# PROTO0001.net
KiCad netlist of a schematic drawn in EAGLE
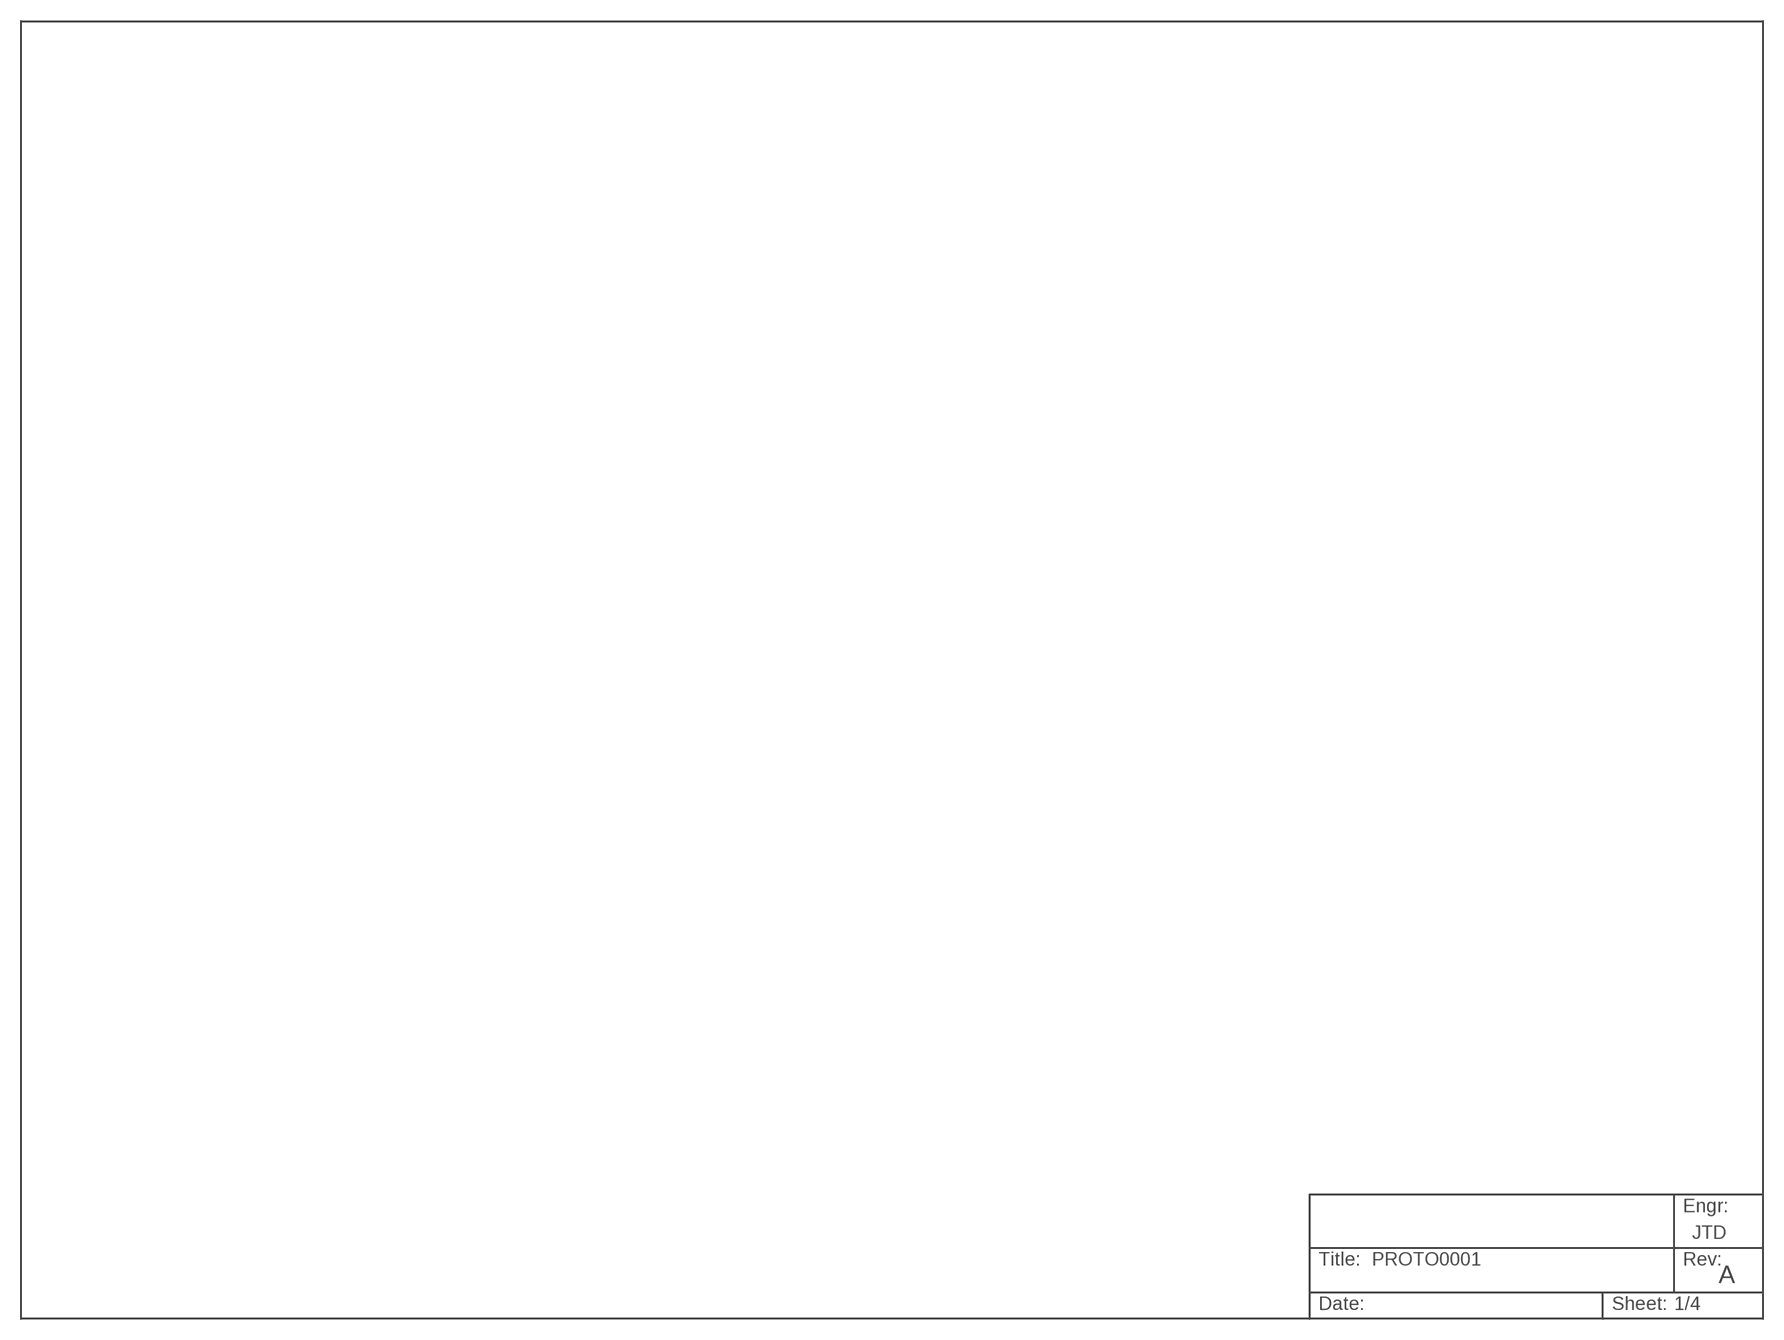
[diagram p0: schematic, sheet 1]
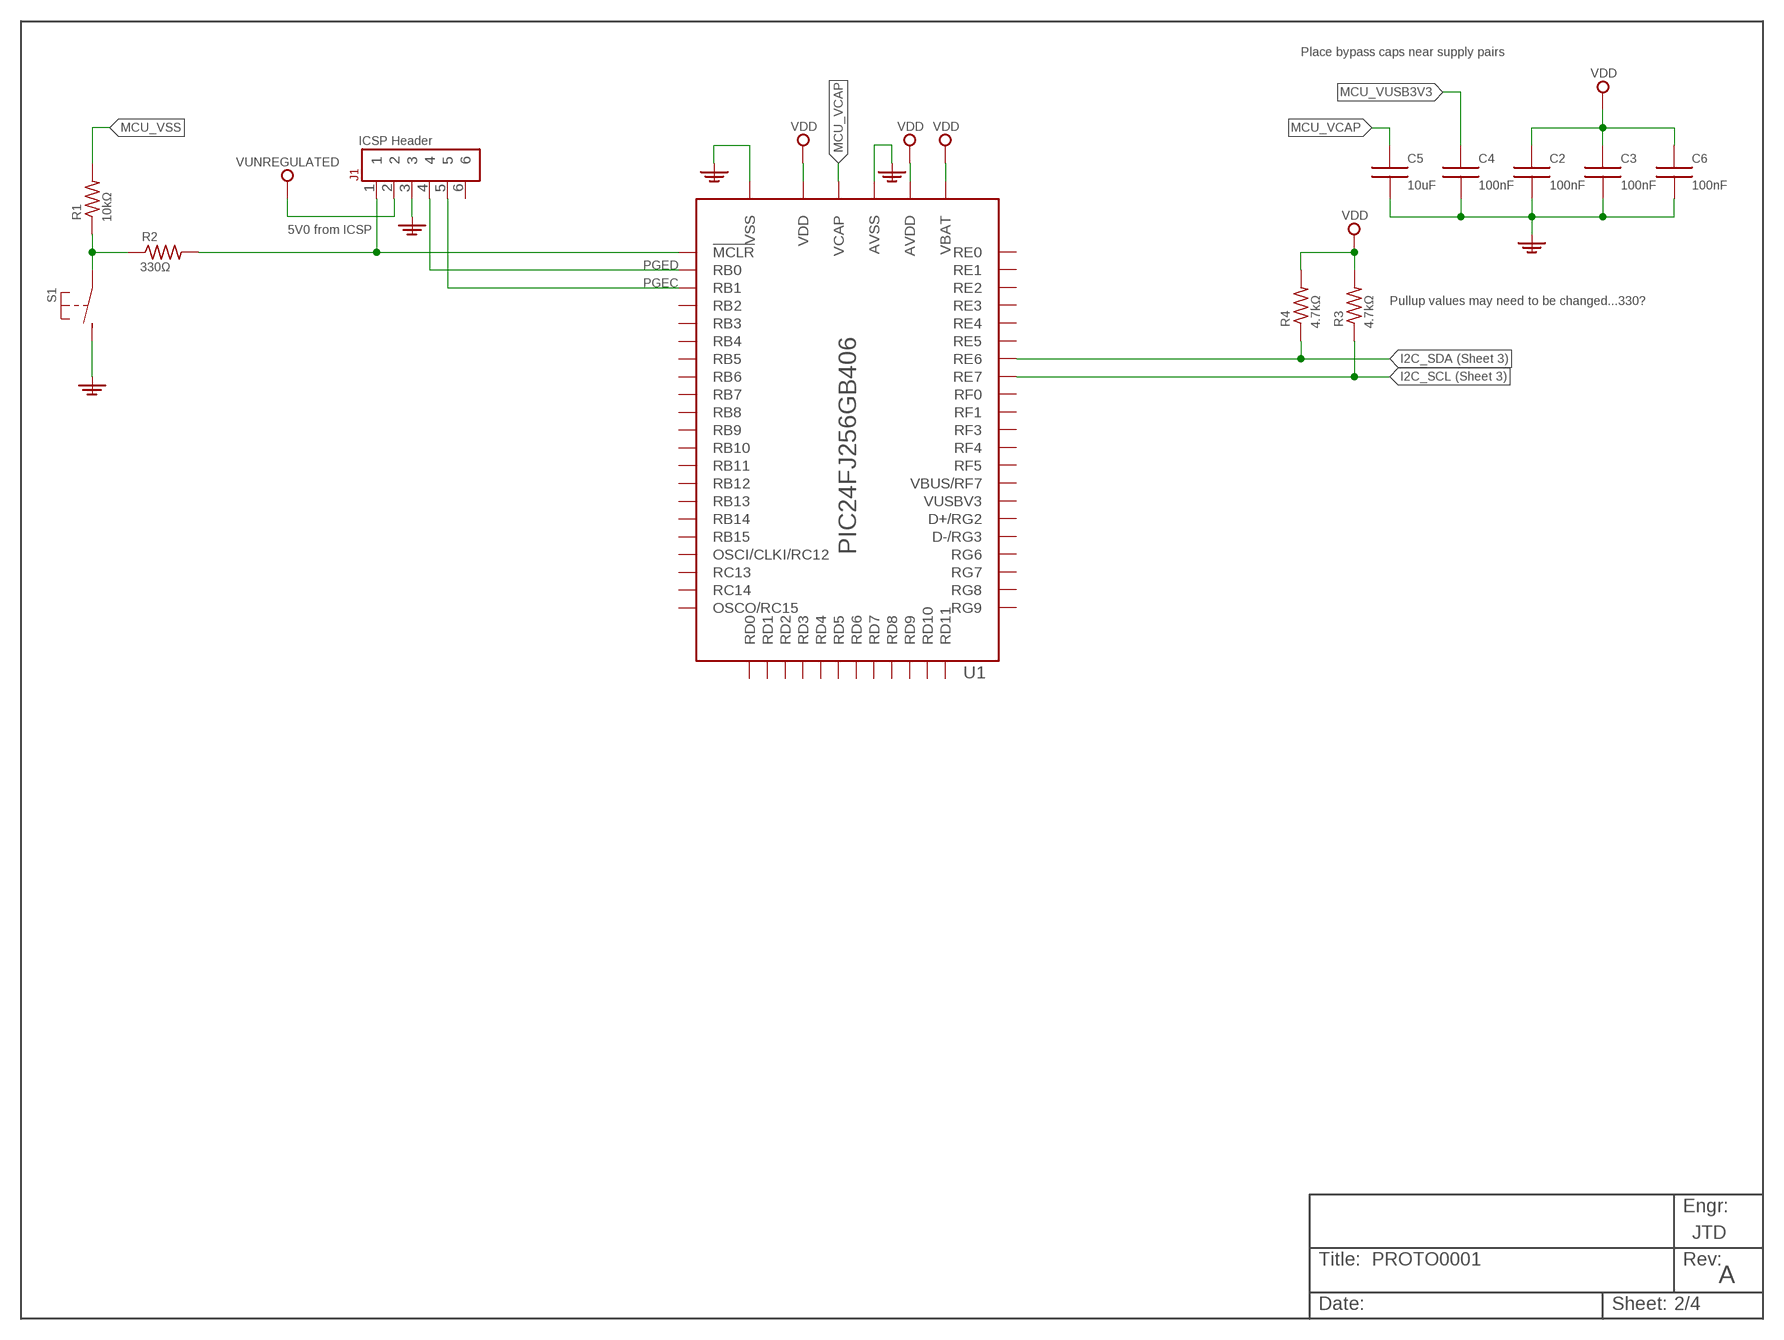
[diagram p1: schematic, sheet 2]
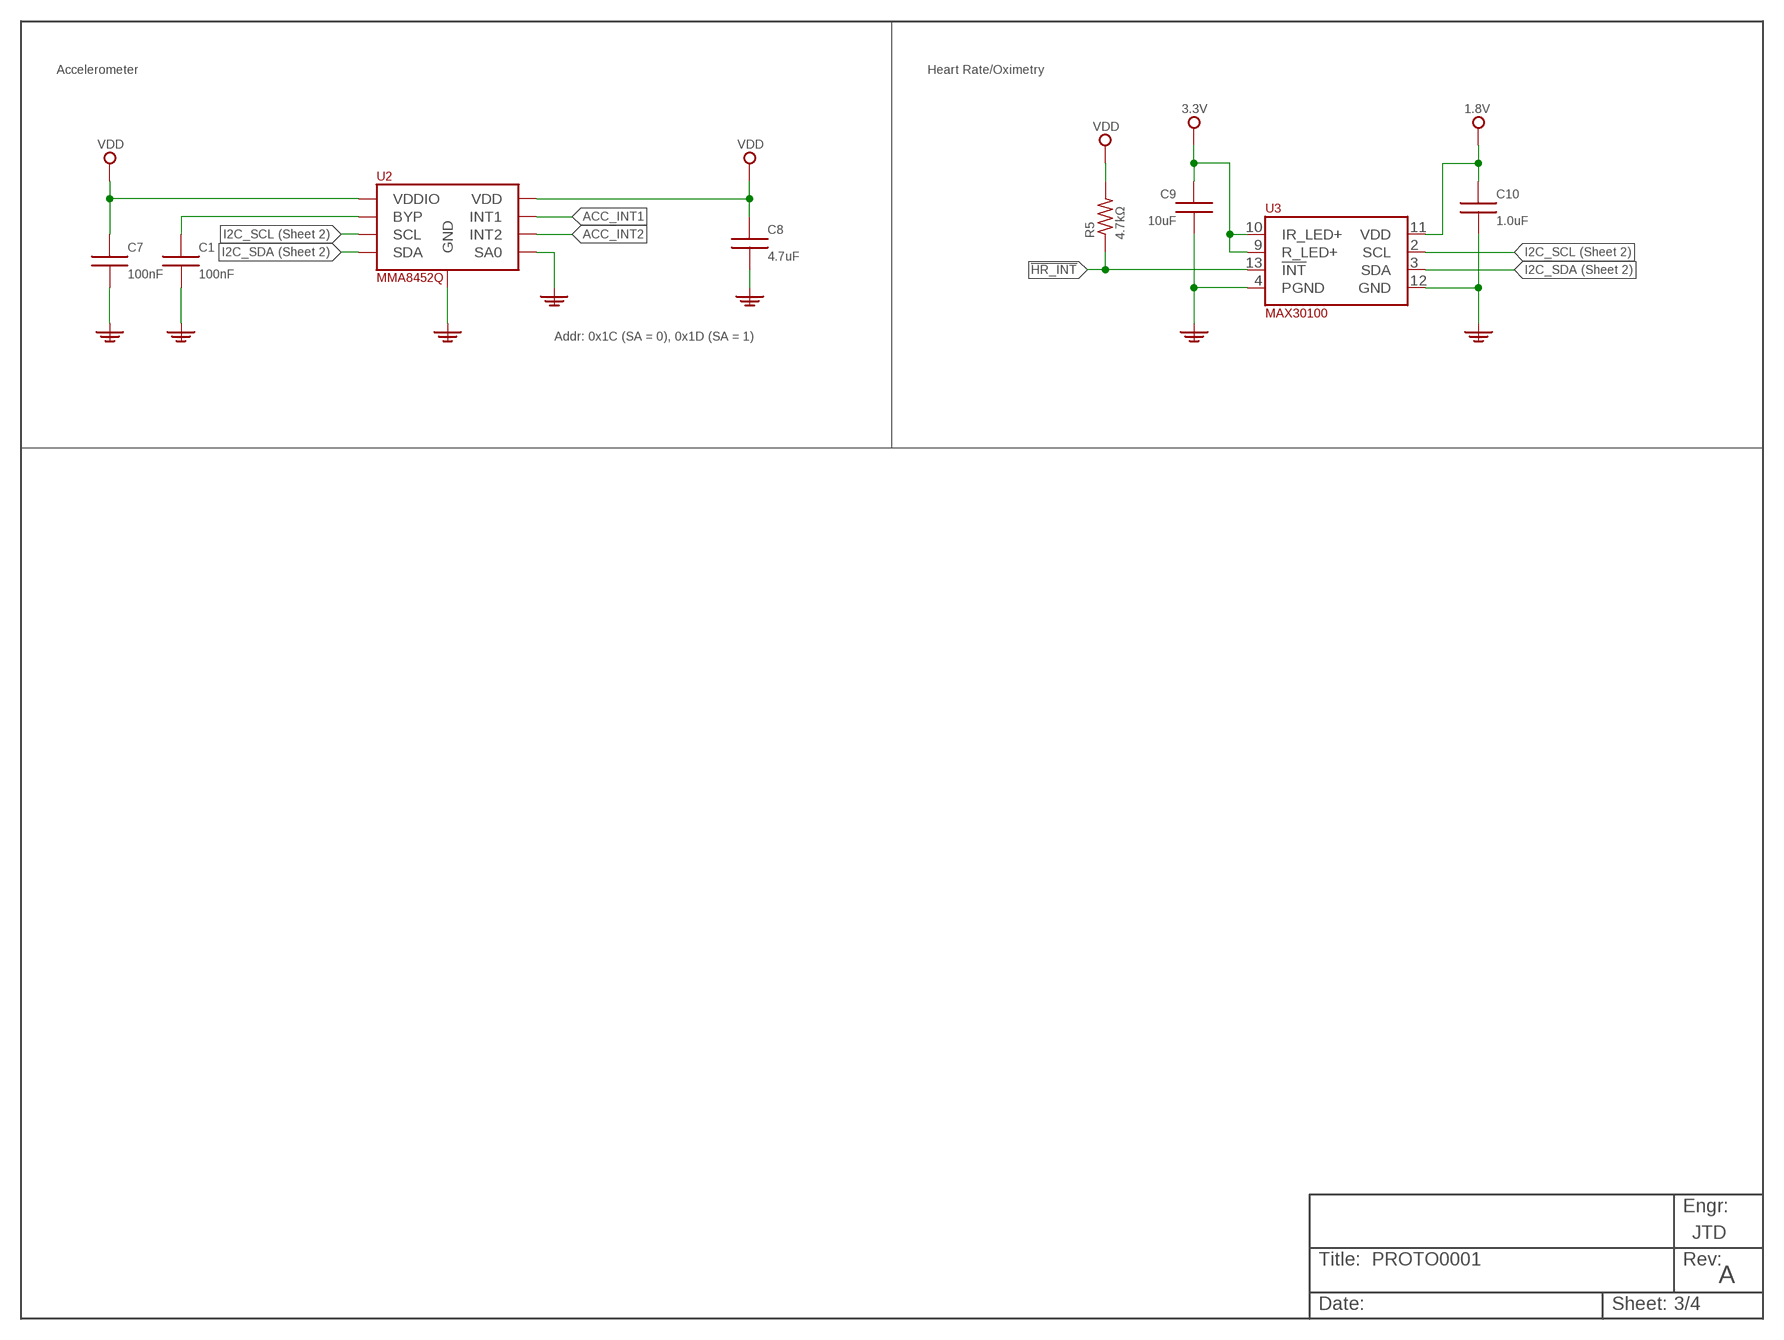
[diagram p2: schematic, sheet 3]
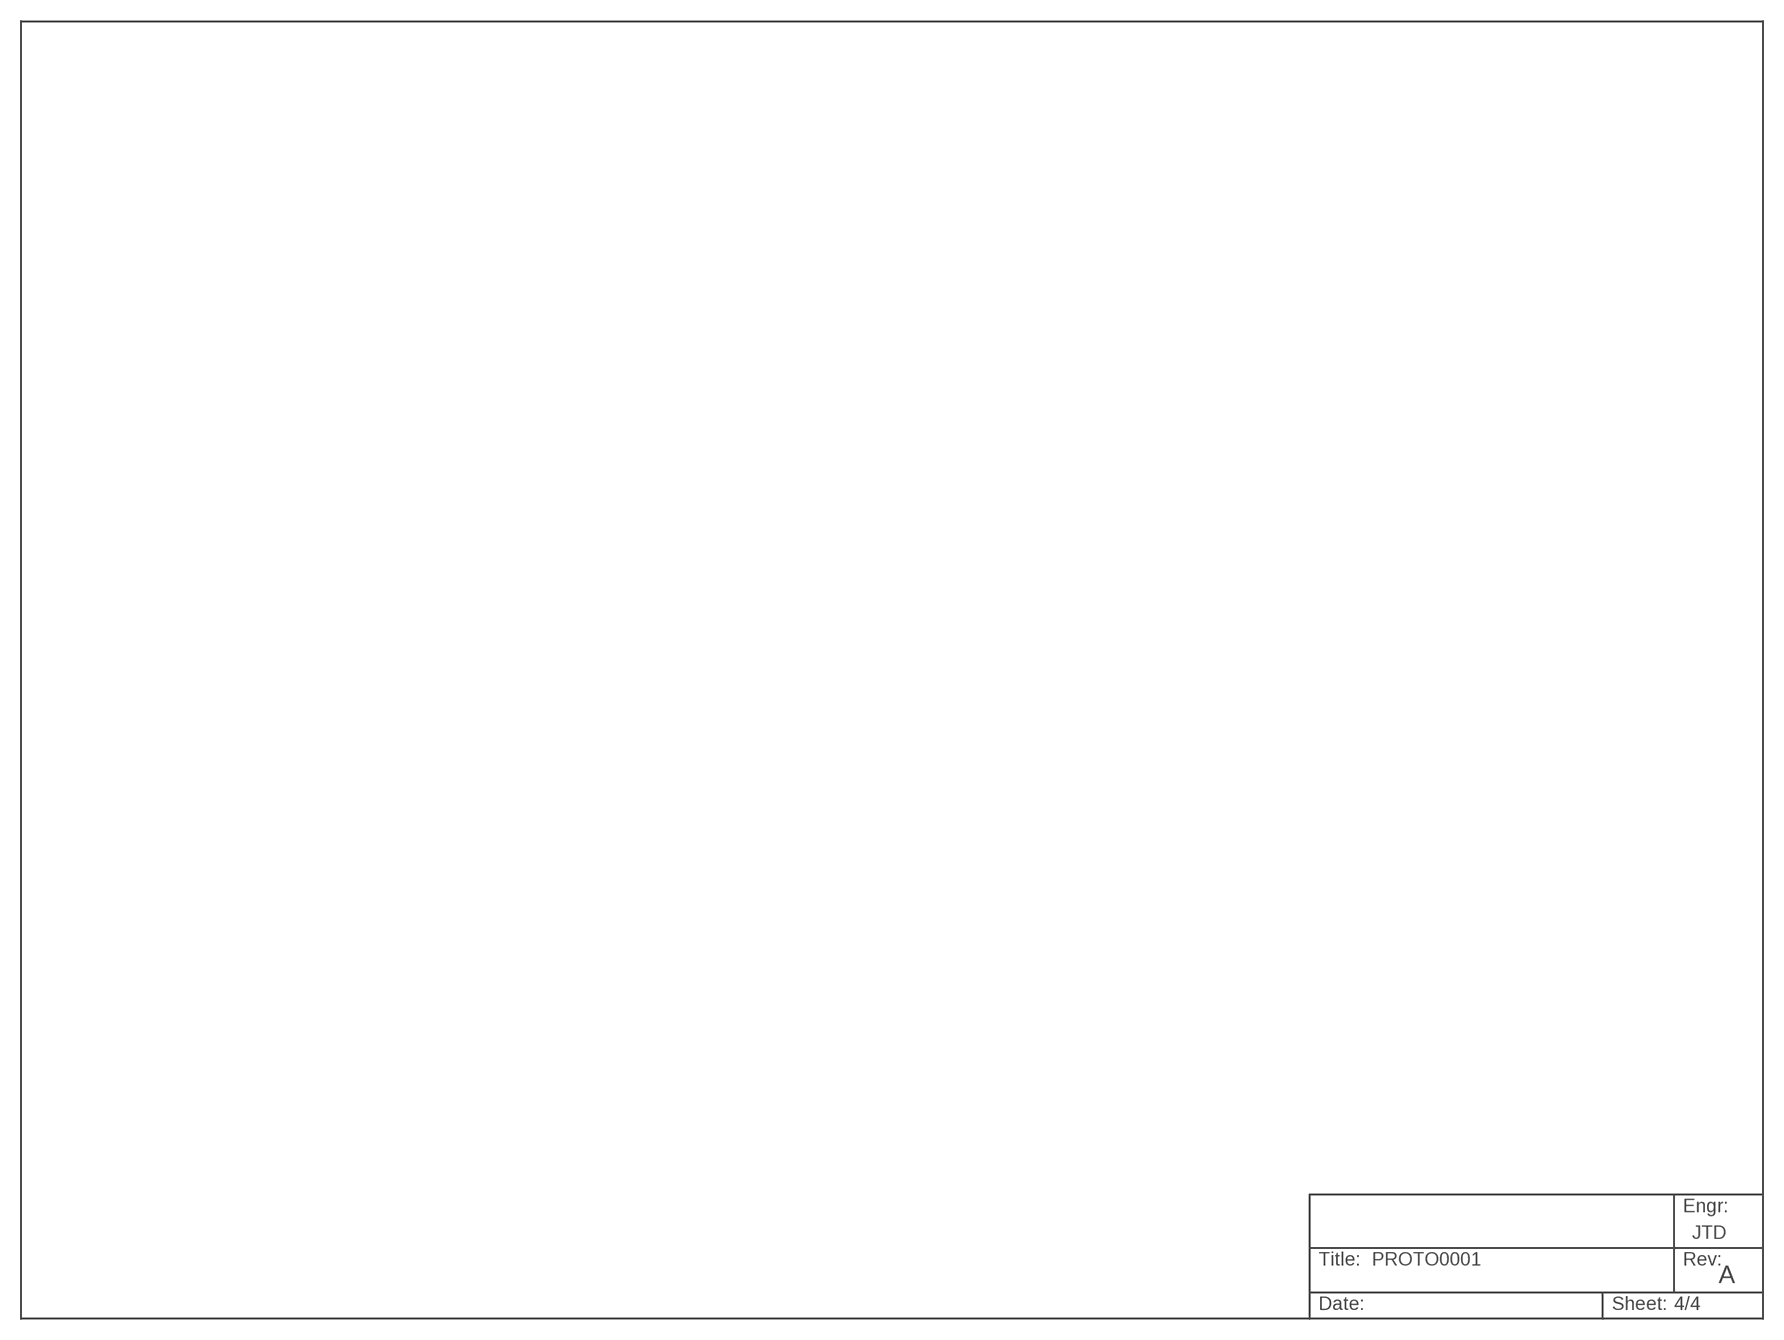
[diagram p3: schematic, sheet 4]

(export (version "E")
  (design (tool "Eeschema 10.0.6"))
  (components
    (comp (ref "C1")
      (value "CAP_100N_0402_CERAMIC")
      (footprint "eagle-import:CAPACITOR_0402")
      (fields
        (field (name "MANUFACTURER") "AVX Corporation")
        (field (name "PARTNO") "04023C104KAT2A")
        (field (name "TOLERANCE") "10%")
      )
      (libsource (lib "eagle-import") (part "CAP_100N_0402_CERAMIC"))
    )
    (comp (ref "C7")
      (value "CAP_100N_0402_CERAMIC")
      (footprint "eagle-import:CAPACITOR_0402")
      (fields
        (field (name "MANUFACTURER") "AVX Corporation")
        (field (name "PARTNO") "04023C104KAT2A")
        (field (name "TOLERANCE") "10%")
      )
      (libsource (lib "eagle-import") (part "CAP_100N_0402_CERAMIC"))
    )
    (comp (ref "C8")
      (value "CAP_4.7U_0603_CERAMIC")
      (footprint "eagle-import:CAPACITOR_0603")
      (fields
        (field (name "MANUFACTURER") "Murata Electronics")
        (field (name "PARTNO") "GRM188R61A475KE15D")
        (field (name "TOLERANCE") "10%")
      )
      (libsource (lib "eagle-import") (part "CAP_4.7U_0603_CERAMIC"))
    )
    (comp (ref "C9")
      (value "CAP_10U_0805_CERAMIC")
      (footprint "eagle-import:CAPACITOR_0805")
      (fields (field (name "MANUFACTURER") "AVX Corporation") (field (name "PARTNO") "0805YD106KAT2A"))
      (libsource (lib "eagle-import") (part "CAP_10U_0805_CERAMIC"))
    )
    (comp (ref "C10")
      (value "CAP_1U_0603_CERAMIC")
      (footprint "eagle-import:CAPACITOR_0603")
      (fields (field (name "MANUFACTURER") "Murata Electronics") (field (name "TOLERANCE") "10%"))
      (libsource (lib "eagle-import") (part "CAP_1U_0603_CERAMIC"))
    )
    (comp (ref "R5")
      (value "RES_4.7K_0402")
      (footprint "eagle-import:RESISTOR_0402")
      (fields (field (name "MANUFACTURER") "Yageo") (field (name "TOLERANCE") "1.0%"))
      (libsource (lib "eagle-import") (part "RES_4.7K_0402"))
    )
    (comp (ref "U2")
      (value "MMA8452Q")
      (footprint "eagle-import:QFN50P300X300X100-16")
      (fields (field (name "MANUFACTURER") "Freescale Semiconductor"))
      (libsource (lib "eagle-import") (part "MMA8452Q"))
    )
    (comp (ref "U3")
      (value "MAX30100")
      (footprint "eagle-import:21-0880")
      (fields (field (name "MANUFACTURER") "Maxim Integrated"))
      (libsource (lib "eagle-import") (part "MAX30100"))
    )
    (comp (ref "C2")
      (value "CAP_100N_0402_CERAMIC")
      (footprint "eagle-import:CAPACITOR_0402")
      (fields
        (field (name "MANUFACTURER") "AVX Corporation")
        (field (name "PARTNO") "04023C104KAT2A")
        (field (name "TOLERANCE") "10%")
      )
      (libsource (lib "eagle-import") (part "CAP_100N_0402_CERAMIC"))
    )
    (comp (ref "C3")
      (value "CAP_100N_0402_CERAMIC")
      (footprint "eagle-import:CAPACITOR_0402")
      (fields
        (field (name "MANUFACTURER") "AVX Corporation")
        (field (name "PARTNO") "04023C104KAT2A")
        (field (name "TOLERANCE") "10%")
      )
      (libsource (lib "eagle-import") (part "CAP_100N_0402_CERAMIC"))
    )
    (comp (ref "C4")
      (value "CAP_100N_0402_CERAMIC")
      (footprint "eagle-import:CAPACITOR_0402")
      (fields
        (field (name "MANUFACTURER") "AVX Corporation")
        (field (name "PARTNO") "04023C104KAT2A")
        (field (name "TOLERANCE") "10%")
      )
      (libsource (lib "eagle-import") (part "CAP_100N_0402_CERAMIC"))
    )
    (comp (ref "C5")
      (value "CAP_10U_0805_CERAMIC")
      (footprint "eagle-import:CAPACITOR_0805")
      (fields (field (name "MANUFACTURER") "AVX Corporation") (field (name "PARTNO") "0805YD106KAT2A"))
      (libsource (lib "eagle-import") (part "CAP_10U_0805_CERAMIC"))
    )
    (comp (ref "C6")
      (value "CAP_100N_0402_CERAMIC")
      (footprint "eagle-import:CAPACITOR_0402")
      (fields
        (field (name "MANUFACTURER") "AVX Corporation")
        (field (name "PARTNO") "04023C104KAT2A")
        (field (name "TOLERANCE") "10%")
      )
      (libsource (lib "eagle-import") (part "CAP_100N_0402_CERAMIC"))
    )
    (comp (ref "J1")
      (value "HEADER_2.54MM_1X6")
      (footprint "eagle-import:HEADER_2.54MM_1X6")
      (libsource (lib "eagle-import") (part "HEADER_2.54MM_1X6"))
    )
    (comp (ref "R1")
      (value "10.0kOhm")
      (footprint "eagle-import:RESISTOR_0402")
      (fields
        (field (name "MANUFACTURER") "Yageo")
        (field (name "PARTNO") "RC0402FR-0710KL")
        (field (name "TOLERANCE") "1.0%")
      )
      (libsource (lib "eagle-import") (part "RES_10K_0402"))
    )
    (comp (ref "R2")
      (value "RES_330_0402")
      (footprint "eagle-import:RESISTOR_0402")
      (fields
        (field (name "MANUFACTURER") "Yageo")
        (field (name "PARTNO") "RC0402FR-07330RL")
        (field (name "TOLERANCE") "1.0%")
      )
      (libsource (lib "eagle-import") (part "RES_330_0402"))
    )
    (comp (ref "R3")
      (value "RES_4.7K_0402")
      (footprint "eagle-import:RESISTOR_0402")
      (fields (field (name "MANUFACTURER") "Yageo") (field (name "TOLERANCE") "1.0%"))
      (libsource (lib "eagle-import") (part "RES_4.7K_0402"))
    )
    (comp (ref "R4")
      (value "RES_4.7K_0402")
      (footprint "eagle-import:RESISTOR_0402")
      (fields (field (name "MANUFACTURER") "Yageo") (field (name "TOLERANCE") "1.0%"))
      (libsource (lib "eagle-import") (part "RES_4.7K_0402"))
    )
    (comp (ref "S1")
      (value "SWITCH_TACTILE_THRU")
      (footprint "eagle-import:SWITCH_TACTILE_THRU")
      (fields (field (name "MANUFACTURER") "C&K Components") (field (name "PARTNUM") "PTS645SM43-2 LFS"))
      (libsource (lib "eagle-import") (part "SWITCH_TACTILE_THRU"))
    )
    (comp (ref "U1")
      (value "PIC24FJ256GB406")
      (footprint "eagle-import:QFP50P1200X1200X120-64L30")
      (fields (field (name "MANUFACTURER") "Microchip"))
      (libsource (lib "eagle-import") (part "PIC24FJ256GB406"))
    )
  )
  (nets
    (net (code "1") (name "1V8") (class "Default")
      (node (ref "C10") (pin "1") (pinfunction "1_1") (pintype "passive"))
      (node (ref "U3") (pin "11") (pinfunction "VDD_11") (pintype "bidirectional"))
    )
    (net (code "2") (name "3V3") (class "Default")
      (node (ref "C9") (pin "1") (pinfunction "1_1") (pintype "passive"))
      (node (ref "U3") (pin "10") (pinfunction "IR_LED+_10") (pintype "bidirectional"))
      (node (ref "U3") (pin "9") (pinfunction "R_LED+_9") (pintype "bidirectional"))
    )
    (net (code "3") (name "5V0") (class "Default")
      (node (ref "C2") (pin "1") (pinfunction "1_1") (pintype "passive"))
      (node (ref "C3") (pin "1") (pinfunction "1_1") (pintype "passive"))
      (node (ref "C6") (pin "1") (pinfunction "1_1") (pintype "passive"))
      (node (ref "C7") (pin "1") (pinfunction "1_1") (pintype "passive"))
      (node (ref "C8") (pin "1") (pinfunction "1_1") (pintype "passive"))
      (node (ref "R3") (pin "2") (pinfunction "2_2") (pintype "passive"))
      (node (ref "R4") (pin "2") (pinfunction "2_2") (pintype "passive"))
      (node (ref "R5") (pin "2") (pinfunction "2_2") (pintype "passive"))
      (node (ref "U1") (pin "10") (pinfunction "VDD_10") (pintype "bidirectional"))
      (node (ref "U1") (pin "19") (pinfunction "AVDD_19") (pintype "bidirectional"))
      (node (ref "U1") (pin "26") (pinfunction "VDD_26") (pintype "bidirectional"))
      (node (ref "U1") (pin "38") (pinfunction "VDD_38") (pintype "bidirectional"))
      (node (ref "U1") (pin "57") (pinfunction "VBAT_57") (pintype "bidirectional"))
      (node (ref "U2") (pin "1") (pinfunction "VDDIO_1") (pintype "bidirectional"))
      (node (ref "U2") (pin "14") (pinfunction "VDD_14") (pintype "bidirectional"))
    )
    (net (code "4") (name "ACC_INT1") (class "Default")
      (node (ref "U2") (pin "11") (pinfunction "INT1_11") (pintype "bidirectional"))
    )
    (net (code "5") (name "ACC_INT2") (class "Default")
      (node (ref "U2") (pin "9") (pinfunction "INT2_9") (pintype "bidirectional"))
    )
    (net (code "6") (name "GND") (class "Default")
      (node (ref "C1") (pin "2") (pinfunction "2_2") (pintype "passive"))
      (node (ref "C10") (pin "2") (pinfunction "2_2") (pintype "passive"))
      (node (ref "C2") (pin "2") (pinfunction "2_2") (pintype "passive"))
      (node (ref "C3") (pin "2") (pinfunction "2_2") (pintype "passive"))
      (node (ref "C4") (pin "2") (pinfunction "2_2") (pintype "passive"))
      (node (ref "C5") (pin "2") (pinfunction "2_2") (pintype "passive"))
      (node (ref "C6") (pin "2") (pinfunction "2_2") (pintype "passive"))
      (node (ref "C7") (pin "2") (pinfunction "2_2") (pintype "passive"))
      (node (ref "C8") (pin "2") (pinfunction "2_2") (pintype "passive"))
      (node (ref "C9") (pin "2") (pinfunction "2_2") (pintype "passive"))
      (node (ref "J1") (pin "3") (pinfunction "3_3") (pintype "bidirectional"))
      (node (ref "S1") (pin "3") (pinfunction "S_3") (pintype "passive"))
      (node (ref "S1") (pin "4") (pinfunction "S_4") (pintype "passive"))
      (node (ref "U1") (pin "20") (pinfunction "AVSS_20") (pintype "bidirectional"))
      (node (ref "U1") (pin "25") (pinfunction "VSS_25") (pintype "bidirectional"))
      (node (ref "U1") (pin "41") (pinfunction "VSS_41") (pintype "bidirectional"))
      (node (ref "U1") (pin "9") (pinfunction "VSS_9") (pintype "bidirectional"))
      (node (ref "U2") (pin "12") (pinfunction "GND_12") (pintype "bidirectional"))
      (node (ref "U2") (pin "5") (pinfunction "GND_5") (pintype "bidirectional"))
      (node (ref "U2") (pin "7") (pinfunction "SA0_7") (pintype "bidirectional"))
      (node (ref "U3") (pin "12") (pinfunction "GND_12") (pintype "bidirectional"))
      (node (ref "U3") (pin "4") (pinfunction "PGND_4") (pintype "bidirectional"))
    )
    (net (code "7") (name "I2C_SCL") (class "Default")
      (node (ref "R3") (pin "1") (pinfunction "1_1") (pintype "passive"))
      (node (ref "U1") (pin "3") (pinfunction "RE7_3") (pintype "bidirectional"))
      (node (ref "U2") (pin "4") (pinfunction "SCL_4") (pintype "bidirectional"))
      (node (ref "U3") (pin "2") (pinfunction "SCL_2") (pintype "bidirectional"))
    )
    (net (code "8") (name "I2C_SDA") (class "Default")
      (node (ref "R4") (pin "1") (pinfunction "1_1") (pintype "passive"))
      (node (ref "U1") (pin "2") (pinfunction "RE6_2") (pintype "bidirectional"))
      (node (ref "U2") (pin "6") (pinfunction "SDA_6") (pintype "bidirectional"))
      (node (ref "U3") (pin "3") (pinfunction "SDA_3") (pintype "bidirectional"))
    )
    (net (code "9") (name "MCU_VCAP") (class "Default")
      (node (ref "C5") (pin "1") (pinfunction "1_1") (pintype "passive"))
      (node (ref "U1") (pin "56") (pinfunction "VCAP_56") (pintype "bidirectional"))
    )
    (net (code "10") (name "MCU_VSS") (class "Default")
      (node (ref "R1") (pin "2") (pinfunction "2_2") (pintype "passive"))
    )
    (net (code "11") (name "MCU_VUSB3V3") (class "Default")
      (node (ref "C4") (pin "1") (pinfunction "1_1") (pintype "passive"))
    )
    (net (code "12") (name "Net-(R1-Pad1)") (class "Default")
      (node (ref "R1") (pin "1") (pinfunction "1_1") (pintype "passive"))
      (node (ref "R2") (pin "1") (pinfunction "1_1") (pintype "passive"))
      (node (ref "S1") (pin "1") (pinfunction "P_1") (pintype "passive"))
      (node (ref "S1") (pin "2") (pinfunction "P_2") (pintype "passive"))
    )
    (net (code "13") (name "Net-(U1-~{MCLR})") (class "Default")
      (node (ref "J1") (pin "1") (pinfunction "1_1") (pintype "bidirectional"))
      (node (ref "R2") (pin "2") (pinfunction "2_2") (pintype "passive"))
      (node (ref "U1") (pin "7") (pinfunction "~{MCLR}_7") (pintype "bidirectional"))
    )
    (net (code "14") (name "Net-(U2-BYP)") (class "Default")
      (node (ref "C1") (pin "1") (pinfunction "1_1") (pintype "passive"))
      (node (ref "U2") (pin "2") (pinfunction "BYP_2") (pintype "bidirectional"))
    )
    (net (code "15") (name "PGEC") (class "Default")
      (node (ref "J1") (pin "5") (pinfunction "5_5") (pintype "bidirectional"))
      (node (ref "U1") (pin "15") (pinfunction "RB1_15") (pintype "bidirectional"))
    )
    (net (code "16") (name "PGED") (class "Default")
      (node (ref "J1") (pin "4") (pinfunction "4_4") (pintype "bidirectional"))
      (node (ref "U1") (pin "16") (pinfunction "RB0_16") (pintype "bidirectional"))
    )
    (net (code "17") (name "VUNREGULATED") (class "Default")
      (node (ref "J1") (pin "2") (pinfunction "2_2") (pintype "bidirectional"))
    )
    (net (code "18") (name "unconnected-(J1-Pad6)") (class "Default")
      (node (ref "J1") (pin "6") (pinfunction "6_6") (pintype "bidirectional"))
    )
    (net (code "19") (name "unconnected-(U1-D+{slash}RG2-Pad37)") (class "Default")
      (node (ref "U1") (pin "37") (pinfunction "D+/RG2_37") (pintype "bidirectional"))
    )
    (net (code "20") (name "unconnected-(U1-D-{slash}RG3-Pad36)") (class "Default")
      (node (ref "U1") (pin "36") (pinfunction "D-/RG3_36") (pintype "bidirectional"))
    )
    (net (code "21") (name "unconnected-(U1-OSCI{slash}CLKI{slash}RC12-Pad39)") (class "Default")
      (node (ref "U1") (pin "39") (pinfunction "OSCI/CLKI/RC12_39") (pintype "bidirectional"))
    )
    (net (code "22") (name "unconnected-(U1-OSCO{slash}RC15-Pad40)") (class "Default")
      (node (ref "U1") (pin "40") (pinfunction "OSCO/RC15_40") (pintype "bidirectional"))
    )
    (net (code "23") (name "unconnected-(U1-RB2-Pad14)") (class "Default")
      (node (ref "U1") (pin "14") (pinfunction "RB2_14") (pintype "bidirectional"))
    )
    (net (code "24") (name "unconnected-(U1-RB3-Pad13)") (class "Default")
      (node (ref "U1") (pin "13") (pinfunction "RB3_13") (pintype "bidirectional"))
    )
    (net (code "25") (name "unconnected-(U1-RB4-Pad12)") (class "Default")
      (node (ref "U1") (pin "12") (pinfunction "RB4_12") (pintype "bidirectional"))
    )
    (net (code "26") (name "unconnected-(U1-RB5-Pad11)") (class "Default")
      (node (ref "U1") (pin "11") (pinfunction "RB5_11") (pintype "bidirectional"))
    )
    (net (code "27") (name "unconnected-(U1-RB6-Pad17)") (class "Default")
      (node (ref "U1") (pin "17") (pinfunction "RB6_17") (pintype "bidirectional"))
    )
    (net (code "28") (name "unconnected-(U1-RB7-Pad18)") (class "Default")
      (node (ref "U1") (pin "18") (pinfunction "RB7_18") (pintype "bidirectional"))
    )
    (net (code "29") (name "unconnected-(U1-RB8-Pad21)") (class "Default")
      (node (ref "U1") (pin "21") (pinfunction "RB8_21") (pintype "bidirectional"))
    )
    (net (code "30") (name "unconnected-(U1-RB9-Pad22)") (class "Default")
      (node (ref "U1") (pin "22") (pinfunction "RB9_22") (pintype "bidirectional"))
    )
    (net (code "31") (name "unconnected-(U1-RB10-Pad23)") (class "Default")
      (node (ref "U1") (pin "23") (pinfunction "RB10_23") (pintype "bidirectional"))
    )
    (net (code "32") (name "unconnected-(U1-RB11-Pad24)") (class "Default")
      (node (ref "U1") (pin "24") (pinfunction "RB11_24") (pintype "bidirectional"))
    )
    (net (code "33") (name "unconnected-(U1-RB12-Pad27)") (class "Default")
      (node (ref "U1") (pin "27") (pinfunction "RB12_27") (pintype "bidirectional"))
    )
    (net (code "34") (name "unconnected-(U1-RB13-Pad28)") (class "Default")
      (node (ref "U1") (pin "28") (pinfunction "RB13_28") (pintype "bidirectional"))
    )
    (net (code "35") (name "unconnected-(U1-RB14-Pad29)") (class "Default")
      (node (ref "U1") (pin "29") (pinfunction "RB14_29") (pintype "bidirectional"))
    )
    (net (code "36") (name "unconnected-(U1-RB15-Pad30)") (class "Default")
      (node (ref "U1") (pin "30") (pinfunction "RB15_30") (pintype "bidirectional"))
    )
    (net (code "37") (name "unconnected-(U1-RC13-Pad47)") (class "Default")
      (node (ref "U1") (pin "47") (pinfunction "RC13_47") (pintype "bidirectional"))
    )
    (net (code "38") (name "unconnected-(U1-RC14-Pad48)") (class "Default")
      (node (ref "U1") (pin "48") (pinfunction "RC14_48") (pintype "bidirectional"))
    )
    (net (code "39") (name "unconnected-(U1-RD0-Pad46)") (class "Default")
      (node (ref "U1") (pin "46") (pinfunction "RD0_46") (pintype "bidirectional"))
    )
    (net (code "40") (name "unconnected-(U1-RD1-Pad49)") (class "Default")
      (node (ref "U1") (pin "49") (pinfunction "RD1_49") (pintype "bidirectional"))
    )
    (net (code "41") (name "unconnected-(U1-RD2-Pad50)") (class "Default")
      (node (ref "U1") (pin "50") (pinfunction "RD2_50") (pintype "bidirectional"))
    )
    (net (code "42") (name "unconnected-(U1-RD3-Pad51)") (class "Default")
      (node (ref "U1") (pin "51") (pinfunction "RD3_51") (pintype "bidirectional"))
    )
    (net (code "43") (name "unconnected-(U1-RD4-Pad52)") (class "Default")
      (node (ref "U1") (pin "52") (pinfunction "RD4_52") (pintype "bidirectional"))
    )
    (net (code "44") (name "unconnected-(U1-RD5-Pad53)") (class "Default")
      (node (ref "U1") (pin "53") (pinfunction "RD5_53") (pintype "bidirectional"))
    )
    (net (code "45") (name "unconnected-(U1-RD6-Pad54)") (class "Default")
      (node (ref "U1") (pin "54") (pinfunction "RD6_54") (pintype "bidirectional"))
    )
    (net (code "46") (name "unconnected-(U1-RD7-Pad55)") (class "Default")
      (node (ref "U1") (pin "55") (pinfunction "RD7_55") (pintype "bidirectional"))
    )
    (net (code "47") (name "unconnected-(U1-RD8-Pad42)") (class "Default")
      (node (ref "U1") (pin "42") (pinfunction "RD8_42") (pintype "bidirectional"))
    )
    (net (code "48") (name "unconnected-(U1-RD9-Pad43)") (class "Default")
      (node (ref "U1") (pin "43") (pinfunction "RD9_43") (pintype "bidirectional"))
    )
    (net (code "49") (name "unconnected-(U1-RD10-Pad44)") (class "Default")
      (node (ref "U1") (pin "44") (pinfunction "RD10_44") (pintype "bidirectional"))
    )
    (net (code "50") (name "unconnected-(U1-RD11-Pad45)") (class "Default")
      (node (ref "U1") (pin "45") (pinfunction "RD11_45") (pintype "bidirectional"))
    )
    (net (code "51") (name "unconnected-(U1-RE0-Pad60)") (class "Default")
      (node (ref "U1") (pin "60") (pinfunction "RE0_60") (pintype "bidirectional"))
    )
    (net (code "52") (name "unconnected-(U1-RE1-Pad61)") (class "Default")
      (node (ref "U1") (pin "61") (pinfunction "RE1_61") (pintype "bidirectional"))
    )
    (net (code "53") (name "unconnected-(U1-RE2-Pad62)") (class "Default")
      (node (ref "U1") (pin "62") (pinfunction "RE2_62") (pintype "bidirectional"))
    )
    (net (code "54") (name "unconnected-(U1-RE3-Pad63)") (class "Default")
      (node (ref "U1") (pin "63") (pinfunction "RE3_63") (pintype "bidirectional"))
    )
    (net (code "55") (name "unconnected-(U1-RE4-Pad64)") (class "Default")
      (node (ref "U1") (pin "64") (pinfunction "RE4_64") (pintype "bidirectional"))
    )
    (net (code "56") (name "unconnected-(U1-RE5-Pad1)") (class "Default")
      (node (ref "U1") (pin "1") (pinfunction "RE5_1") (pintype "bidirectional"))
    )
    (net (code "57") (name "unconnected-(U1-RF0-Pad58)") (class "Default")
      (node (ref "U1") (pin "58") (pinfunction "RF0_58") (pintype "bidirectional"))
    )
    (net (code "58") (name "unconnected-(U1-RF1-Pad59)") (class "Default")
      (node (ref "U1") (pin "59") (pinfunction "RF1_59") (pintype "bidirectional"))
    )
    (net (code "59") (name "unconnected-(U1-RF3-Pad33)") (class "Default")
      (node (ref "U1") (pin "33") (pinfunction "RF3_33") (pintype "bidirectional"))
    )
    (net (code "60") (name "unconnected-(U1-RF4-Pad31)") (class "Default")
      (node (ref "U1") (pin "31") (pinfunction "RF4_31") (pintype "bidirectional"))
    )
    (net (code "61") (name "unconnected-(U1-RF5-Pad32)") (class "Default")
      (node (ref "U1") (pin "32") (pinfunction "RF5_32") (pintype "bidirectional"))
    )
    (net (code "62") (name "unconnected-(U1-RG6-Pad4)") (class "Default")
      (node (ref "U1") (pin "4") (pinfunction "RG6_4") (pintype "bidirectional"))
    )
    (net (code "63") (name "unconnected-(U1-RG7-Pad5)") (class "Default")
      (node (ref "U1") (pin "5") (pinfunction "RG7_5") (pintype "bidirectional"))
    )
    (net (code "64") (name "unconnected-(U1-RG8-Pad6)") (class "Default")
      (node (ref "U1") (pin "6") (pinfunction "RG8_6") (pintype "bidirectional"))
    )
    (net (code "65") (name "unconnected-(U1-RG9-Pad8)") (class "Default")
      (node (ref "U1") (pin "8") (pinfunction "RG9_8") (pintype "bidirectional"))
    )
    (net (code "66") (name "unconnected-(U1-VBUS{slash}RF7-Pad34)") (class "Default")
      (node (ref "U1") (pin "34") (pinfunction "VBUS/RF7_34") (pintype "bidirectional"))
    )
    (net (code "67") (name "unconnected-(U1-VUSBV3-Pad35)") (class "Default")
      (node (ref "U1") (pin "35") (pinfunction "VUSBV3_35") (pintype "bidirectional"))
    )
    (net (code "68") (name "~{HR_INT}") (class "Default")
      (node (ref "R5") (pin "1") (pinfunction "1_1") (pintype "passive"))
      (node (ref "U3") (pin "13") (pinfunction "~{INT}_13") (pintype "bidirectional"))
    )
  )
)
